# Sheet1.net
KiCad netlist of a schematic drawn in Altium Designer
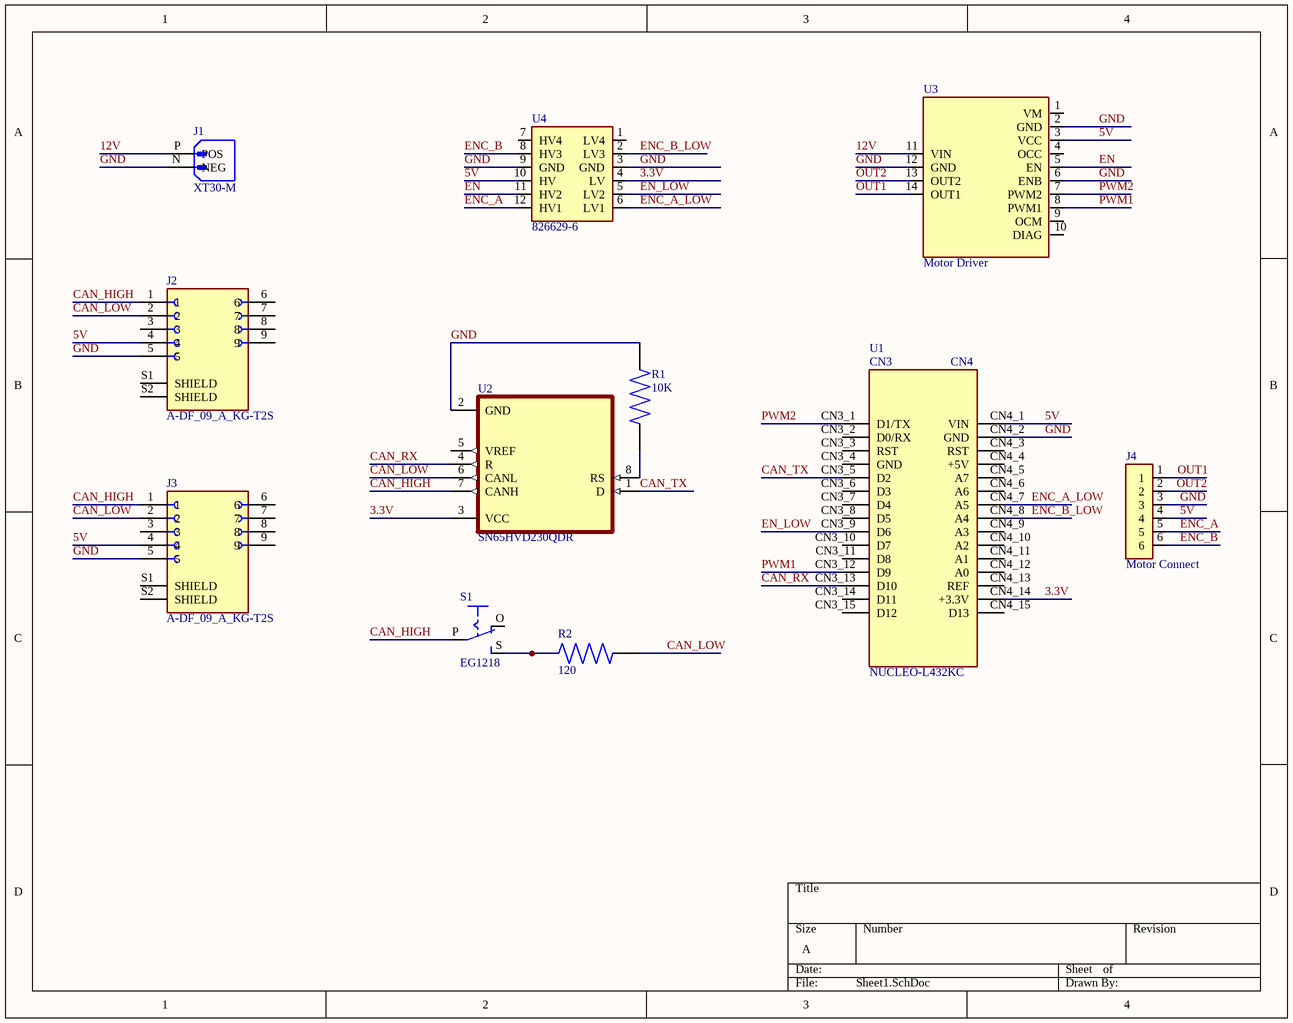
[diagram p0: Sheet1.SchDoc]

(export (version "E")
  (design (tool "Eeschema 10.0.6"))
  (components
    (comp (ref "J1")
      (value "XT30-M")
      (footprint "AMASS_XT60-M")
      (description "Plug; DC supply; XT60; male; PIN: 2; for cable; soldered; 30A; 500V")
      (fields (field (name "MP") "XT60-M") (field (name "MF") "AMASS"))
      (libsource (lib "XT30-M") (part "XT30-M"))
    )
    (comp (ref "J2")
      (value "A-DF_09_A_KG-T2S")
      (footprint "ASSMANN_A-DF_09_A_KG-T2S")
      (description "9 Position D-Sub Receptacle, Female Sockets Connector")
      (fields (field (name "MF") "Assmann WSW") (field (name "MP") "A-DF 09 A/KG-T2S"))
      (libsource (lib "A-DF_09_A_KG-T2S") (part "A-DF_09_A_KG-T2S"))
    )
    (comp (ref "J3")
      (value "A-DF_09_A_KG-T2S")
      (footprint "ASSMANN_A-DF_09_A_KG-T2S")
      (description "9 Position D-Sub Receptacle, Female Sockets Connector")
      (fields (field (name "MF") "Assmann WSW") (field (name "MP") "A-DF 09 A/KG-T2S"))
      (libsource (lib "A-DF_09_A_KG-T2S") (part "A-DF_09_A_KG-T2S"))
    )
    (comp (ref "J4")
      (value "Motor Connect")
      (footprint "HDRV6W63P254_6X1_1524X250X950")
      (description "Conn Unshrouded Header HDR 6 POS 2.54mm Solder ST Thru-Hole Automotive Carton")
      (fields (field (name "MP") "826629-6") (field (name "MF") "TE Connectivity"))
      (libsource (lib "826629-6") (part "826629-6"))
    )
    (comp (ref "R1")
      (value "10K")
      (footprint "RESC3216X65N:RESC3216X65N")
      (fields (field (name "MP") "KTR18EZPF9530"))
      (libsource (lib "KTR18EZPF9530") (part "KTR18EZPF9530"))
    )
    (comp (ref "R2")
      (value "120")
      (footprint "RESC3216X65N:RESC3216X65N")
      (fields (field (name "MP") "KTR18EZPF9530"))
      (libsource (lib "KTR18EZPF9530") (part "KTR18EZPF9530"))
    )
    (comp (ref "S1") (value "EG1218") (footprint "EG1218:EG1218") (libsource (lib "EG1218") (part "EG1218")))
    (comp (ref "U1")
      (value "NUCLEO-L432KC")
      (footprint "MODULE_NUCLEO-L432KC")
      (description "STM32 Nucleo-32 development board with STM32L432KC MCU, supports Arduino connectivity")
      (libsource (lib "NUCLEO-L432KC") (part "NUCLEO-L432KC"))
    )
    (comp (ref "U2")
      (value "SN65HVD230QDR")
      (footprint "SOIC127P599X175-8N")
      (description "3.3-V CAN Transceiver with Standby Mode 8-SOIC -40 to 125")
      (fields (field (name "MF") "Texas Instruments"))
      (libsource (lib "SN65HVD230QDR") (part "SN65HVD230QDR"))
    )
    (comp (ref "U3")
      (value "Motor Driver")
      (footprint "SnapEDApcb:TE_826629-8")
      (description "Conn Unshrouded Header HDR 8 POS 2.54mm Solder ST Thru-Hole Automotive Box")
      (fields (field (name "MP") "826629-8") (field (name "MF") "TE Connectivity"))
      (libsource (lib "Pololu Motor Driver") (part "826629-8"))
    )
    (comp (ref "U4")
      (value "826629-6")
      (footprint "Level Converter:HDRV6W63P254_6X1_1524X250X950")
      (description "Conn Unshrouded Header HDR 6 POS 2.54mm Solder ST Thru-Hole Automotive Carton")
      (fields (field (name "MF") "TE Connectivity"))
      (libsource (lib "Level Converter") (part "826629-6"))
    )
  )
  (nets
    (net (code "1") (name "/3.3V") (class "Default")
      (node (ref "U1") (pin "CN4_14") (pinfunction "+3.3V_CN4_14") (pintype "power_in"))
      (node (ref "U2") (pin "3") (pinfunction "VCC_3") (pintype "power_in"))
      (node (ref "U4") (pin "4") (pinfunction "LV_4") (pintype "passive"))
    )
    (net (code "2") (name "/5V") (class "Default")
      (node (ref "J2") (pin "4") (pinfunction "4_4") (pintype "passive"))
      (node (ref "J3") (pin "4") (pinfunction "4_4") (pintype "passive"))
      (node (ref "J4") (pin "4") (pinfunction "4_4") (pintype "passive"))
      (node (ref "U1") (pin "CN4_1") (pinfunction "VIN_CN4_1") (pintype "power_in"))
      (node (ref "U3") (pin "3") (pinfunction "VCC_3") (pintype "passive"))
      (node (ref "U4") (pin "10") (pinfunction "HV_10") (pintype "passive"))
    )
    (net (code "3") (name "/12V") (class "Default")
      (node (ref "J1") (pin "P") (pinfunction "POS_P") (pintype "passive"))
      (node (ref "U3") (pin "11") (pinfunction "VIN_11") (pintype "passive"))
    )
    (net (code "4") (name "/CAN_HIGH") (class "Default")
      (node (ref "J2") (pin "1") (pinfunction "1_1") (pintype "passive"))
      (node (ref "J3") (pin "1") (pinfunction "1_1") (pintype "passive"))
      (node (ref "S1") (pin "P") (pinfunction "P_P") (pintype "passive"))
      (node (ref "U2") (pin "7") (pinfunction "CANH_7") (pintype "output"))
    )
    (net (code "5") (name "/CAN_LOW") (class "Default")
      (node (ref "J2") (pin "2") (pinfunction "2_2") (pintype "passive"))
      (node (ref "J3") (pin "2") (pinfunction "2_2") (pintype "passive"))
      (node (ref "R2") (pin "1") (pinfunction "1_1") (pintype "passive"))
      (node (ref "U2") (pin "6") (pinfunction "CANL_6") (pintype "output"))
    )
    (net (code "6") (name "/CAN_RX") (class "Default")
      (node (ref "U1") (pin "CN3_13") (pinfunction "D10_CN3_13") (pintype "passive"))
      (node (ref "U2") (pin "4") (pinfunction "R_4") (pintype "output"))
    )
    (net (code "7") (name "/CAN_TX") (class "Default")
      (node (ref "U1") (pin "CN3_5") (pinfunction "D2_CN3_5") (pintype "power_in"))
      (node (ref "U2") (pin "1") (pinfunction "D_1") (pintype "input"))
    )
    (net (code "8") (name "/EN") (class "Default")
      (node (ref "U3") (pin "5") (pinfunction "EN_5") (pintype "passive"))
      (node (ref "U4") (pin "11") (pinfunction "HV2_11") (pintype "passive"))
    )
    (net (code "9") (name "/ENC_A") (class "Default")
      (node (ref "J4") (pin "5") (pinfunction "5_5") (pintype "passive"))
      (node (ref "U4") (pin "12") (pinfunction "HV1_12") (pintype "passive"))
    )
    (net (code "10") (name "/ENC_A_LOW") (class "Default")
      (node (ref "U1") (pin "CN4_7") (pinfunction "A5_CN4_7") (pintype "passive"))
      (node (ref "U4") (pin "6") (pinfunction "LV1_6") (pintype "passive"))
    )
    (net (code "11") (name "/ENC_B") (class "Default")
      (node (ref "J4") (pin "6") (pinfunction "6_6") (pintype "passive"))
      (node (ref "U4") (pin "8") (pinfunction "HV3_8") (pintype "passive"))
    )
    (net (code "12") (name "/ENC_B_LOW") (class "Default")
      (node (ref "U1") (pin "CN4_8") (pinfunction "A4_CN4_8") (pintype "passive"))
      (node (ref "U4") (pin "2") (pinfunction "LV3_2") (pintype "passive"))
    )
    (net (code "13") (name "/EN_LOW") (class "Default")
      (node (ref "U1") (pin "CN3_9") (pinfunction "D6_CN3_9") (pintype "power_in"))
      (node (ref "U4") (pin "5") (pinfunction "LV2_5") (pintype "passive"))
    )
    (net (code "14") (name "/GND") (class "Default")
      (node (ref "J1") (pin "N") (pinfunction "NEG_N") (pintype "passive"))
      (node (ref "J2") (pin "5") (pinfunction "5_5") (pintype "passive"))
      (node (ref "J3") (pin "5") (pinfunction "5_5") (pintype "passive"))
      (node (ref "J4") (pin "3") (pinfunction "3_3") (pintype "passive"))
      (node (ref "R1") (pin "2") (pinfunction "2_2") (pintype "passive"))
      (node (ref "U1") (pin "CN4_2") (pinfunction "GND_CN4_2") (pintype "power_in"))
      (node (ref "U2") (pin "2") (pinfunction "GND_2") (pintype "power_in"))
      (node (ref "U3") (pin "12") (pinfunction "GND_12") (pintype "passive"))
      (node (ref "U3") (pin "2") (pinfunction "GND_2") (pintype "passive"))
      (node (ref "U3") (pin "6") (pinfunction "ENB_6") (pintype "passive"))
      (node (ref "U4") (pin "3") (pinfunction "GND_3") (pintype "passive"))
      (node (ref "U4") (pin "9") (pinfunction "GND_9") (pintype "passive"))
    )
    (net (code "15") (name "/OUT1") (class "Default")
      (node (ref "J4") (pin "1") (pinfunction "1_1") (pintype "passive"))
      (node (ref "U3") (pin "14") (pinfunction "OUT1_14") (pintype "passive"))
    )
    (net (code "16") (name "/OUT2") (class "Default")
      (node (ref "J4") (pin "2") (pinfunction "2_2") (pintype "passive"))
      (node (ref "U3") (pin "13") (pinfunction "OUT2_13") (pintype "passive"))
    )
    (net (code "17") (name "/PWM1") (class "Default")
      (node (ref "U1") (pin "CN3_12") (pinfunction "D9_CN3_12") (pintype "power_in"))
      (node (ref "U3") (pin "8") (pinfunction "PWM1_8") (pintype "passive"))
    )
    (net (code "18") (name "/PWM2") (class "Default")
      (node (ref "U1") (pin "CN3_1") (pinfunction "D1/TX_CN3_1") (pintype "power_in"))
      (node (ref "U3") (pin "7") (pinfunction "PWM2_7") (pintype "passive"))
    )
    (net (code "19") (name "Net-(R2-Pad2)") (class "Default")
      (node (ref "R2") (pin "2") (pinfunction "2_2") (pintype "passive"))
      (node (ref "S1") (pin "S") (pinfunction "S_S") (pintype "passive"))
    )
    (net (code "20") (name "Net-(U2-RS)") (class "Default")
      (node (ref "R1") (pin "1") (pinfunction "1_1") (pintype "passive"))
      (node (ref "U2") (pin "8") (pinfunction "RS_8") (pintype "input"))
    )
    (net (code "21") (name "unconnected-(J2-Pad3)") (class "Default")
      (node (ref "J2") (pin "3") (pinfunction "3_3") (pintype "passive"))
    )
    (net (code "22") (name "unconnected-(J2-Pad6)") (class "Default")
      (node (ref "J2") (pin "6") (pinfunction "6_6") (pintype "passive"))
    )
    (net (code "23") (name "unconnected-(J2-Pad7)") (class "Default")
      (node (ref "J2") (pin "7") (pinfunction "7_7") (pintype "passive"))
    )
    (net (code "24") (name "unconnected-(J2-Pad8)") (class "Default")
      (node (ref "J2") (pin "8") (pinfunction "8_8") (pintype "passive"))
    )
    (net (code "25") (name "unconnected-(J2-Pad9)") (class "Default")
      (node (ref "J2") (pin "9") (pinfunction "9_9") (pintype "passive"))
    )
    (net (code "26") (name "unconnected-(J2-SHIELD-PadS1)") (class "Default")
      (node (ref "J2") (pin "S1") (pinfunction "SHIELD_S1") (pintype "passive"))
    )
    (net (code "27") (name "unconnected-(J2-SHIELD-PadS2)") (class "Default")
      (node (ref "J2") (pin "S2") (pinfunction "SHIELD_S2") (pintype "passive"))
    )
    (net (code "28") (name "unconnected-(J3-Pad3)") (class "Default")
      (node (ref "J3") (pin "3") (pinfunction "3_3") (pintype "passive"))
    )
    (net (code "29") (name "unconnected-(J3-Pad6)") (class "Default")
      (node (ref "J3") (pin "6") (pinfunction "6_6") (pintype "passive"))
    )
    (net (code "30") (name "unconnected-(J3-Pad7)") (class "Default")
      (node (ref "J3") (pin "7") (pinfunction "7_7") (pintype "passive"))
    )
    (net (code "31") (name "unconnected-(J3-Pad8)") (class "Default")
      (node (ref "J3") (pin "8") (pinfunction "8_8") (pintype "passive"))
    )
    (net (code "32") (name "unconnected-(J3-Pad9)") (class "Default")
      (node (ref "J3") (pin "9") (pinfunction "9_9") (pintype "passive"))
    )
    (net (code "33") (name "unconnected-(J3-SHIELD-PadS1)") (class "Default")
      (node (ref "J3") (pin "S1") (pinfunction "SHIELD_S1") (pintype "passive"))
    )
    (net (code "34") (name "unconnected-(J3-SHIELD-PadS2)") (class "Default")
      (node (ref "J3") (pin "S2") (pinfunction "SHIELD_S2") (pintype "passive"))
    )
    (net (code "35") (name "unconnected-(S1-PadO)") (class "Default")
      (node (ref "S1") (pin "O") (pinfunction "O_O") (pintype "passive"))
    )
    (net (code "36") (name "unconnected-(U1-+5V-PadCN4_4)") (class "Default")
      (node (ref "U1") (pin "CN4_4") (pinfunction "+5V_CN4_4") (pintype "power_in"))
    )
    (net (code "37") (name "unconnected-(U1-A0-PadCN4_12)") (class "Default")
      (node (ref "U1") (pin "CN4_12") (pinfunction "A0_CN4_12") (pintype "passive"))
    )
    (net (code "38") (name "unconnected-(U1-A1-PadCN4_11)") (class "Default")
      (node (ref "U1") (pin "CN4_11") (pinfunction "A1_CN4_11") (pintype "passive"))
    )
    (net (code "39") (name "unconnected-(U1-A2-PadCN4_10)") (class "Default")
      (node (ref "U1") (pin "CN4_10") (pinfunction "A2_CN4_10") (pintype "passive"))
    )
    (net (code "40") (name "unconnected-(U1-A3-PadCN4_9)") (class "Default")
      (node (ref "U1") (pin "CN4_9") (pinfunction "A3_CN4_9") (pintype "passive"))
    )
    (net (code "41") (name "unconnected-(U1-A6-PadCN4_6)") (class "Default")
      (node (ref "U1") (pin "CN4_6") (pinfunction "A6_CN4_6") (pintype "passive"))
    )
    (net (code "42") (name "unconnected-(U1-A7-PadCN4_5)") (class "Default")
      (node (ref "U1") (pin "CN4_5") (pinfunction "A7_CN4_5") (pintype "passive"))
    )
    (net (code "43") (name "unconnected-(U1-D0{slash}RX-PadCN3_2)") (class "Default")
      (node (ref "U1") (pin "CN3_2") (pinfunction "D0/RX_CN3_2") (pintype "power_in"))
    )
    (net (code "44") (name "unconnected-(U1-D3-PadCN3_6)") (class "Default")
      (node (ref "U1") (pin "CN3_6") (pinfunction "D3_CN3_6") (pintype "power_in"))
    )
    (net (code "45") (name "unconnected-(U1-D4-PadCN3_7)") (class "Default")
      (node (ref "U1") (pin "CN3_7") (pinfunction "D4_CN3_7") (pintype "power_in"))
    )
    (net (code "46") (name "unconnected-(U1-D5-PadCN3_8)") (class "Default")
      (node (ref "U1") (pin "CN3_8") (pinfunction "D5_CN3_8") (pintype "power_in"))
    )
    (net (code "47") (name "unconnected-(U1-D7-PadCN3_10)") (class "Default")
      (node (ref "U1") (pin "CN3_10") (pinfunction "D7_CN3_10") (pintype "power_in"))
    )
    (net (code "48") (name "unconnected-(U1-D8-PadCN3_11)") (class "Default")
      (node (ref "U1") (pin "CN3_11") (pinfunction "D8_CN3_11") (pintype "power_in"))
    )
    (net (code "49") (name "unconnected-(U1-D11-PadCN3_14)") (class "Default")
      (node (ref "U1") (pin "CN3_14") (pinfunction "D11_CN3_14") (pintype "power_in"))
    )
    (net (code "50") (name "unconnected-(U1-D12-PadCN3_15)") (class "Default")
      (node (ref "U1") (pin "CN3_15") (pinfunction "D12_CN3_15") (pintype "power_in"))
    )
    (net (code "51") (name "unconnected-(U1-D13-PadCN4_15)") (class "Default")
      (node (ref "U1") (pin "CN4_15") (pinfunction "D13_CN4_15") (pintype "power_in"))
    )
    (net (code "52") (name "unconnected-(U1-GND-PadCN3_4)") (class "Default")
      (node (ref "U1") (pin "CN3_4") (pinfunction "GND_CN3_4") (pintype "power_in"))
    )
    (net (code "53") (name "unconnected-(U1-REF-PadCN4_13)") (class "Default")
      (node (ref "U1") (pin "CN4_13") (pinfunction "REF_CN4_13") (pintype "passive"))
    )
    (net (code "54") (name "unconnected-(U1-RST-PadCN3_3)") (class "Default")
      (node (ref "U1") (pin "CN3_3") (pinfunction "RST_CN3_3") (pintype "power_in"))
    )
    (net (code "55") (name "unconnected-(U1-RST-PadCN4_3)") (class "Default")
      (node (ref "U1") (pin "CN4_3") (pinfunction "RST_CN4_3") (pintype "passive"))
    )
    (net (code "56") (name "unconnected-(U2-VREF-Pad5)") (class "Default")
      (node (ref "U2") (pin "5") (pinfunction "VREF_5") (pintype "output"))
    )
    (net (code "57") (name "unconnected-(U3-DIAG-Pad10)") (class "Default")
      (node (ref "U3") (pin "10") (pinfunction "DIAG_10") (pintype "passive"))
    )
    (net (code "58") (name "unconnected-(U3-OCC-Pad4)") (class "Default")
      (node (ref "U3") (pin "4") (pinfunction "OCC_4") (pintype "passive"))
    )
    (net (code "59") (name "unconnected-(U3-OCM-Pad9)") (class "Default")
      (node (ref "U3") (pin "9") (pinfunction "OCM_9") (pintype "passive"))
    )
    (net (code "60") (name "unconnected-(U3-VM-Pad1)") (class "Default")
      (node (ref "U3") (pin "1") (pinfunction "VM_1") (pintype "passive"))
    )
    (net (code "61") (name "unconnected-(U4-HV4-Pad7)") (class "Default")
      (node (ref "U4") (pin "7") (pinfunction "HV4_7") (pintype "passive"))
    )
    (net (code "62") (name "unconnected-(U4-LV4-Pad1)") (class "Default")
      (node (ref "U4") (pin "1") (pinfunction "LV4_1") (pintype "passive"))
    )
  )
)
